# tactBell_revA.net
KiCad netlist of a schematic drawn in EAGLE
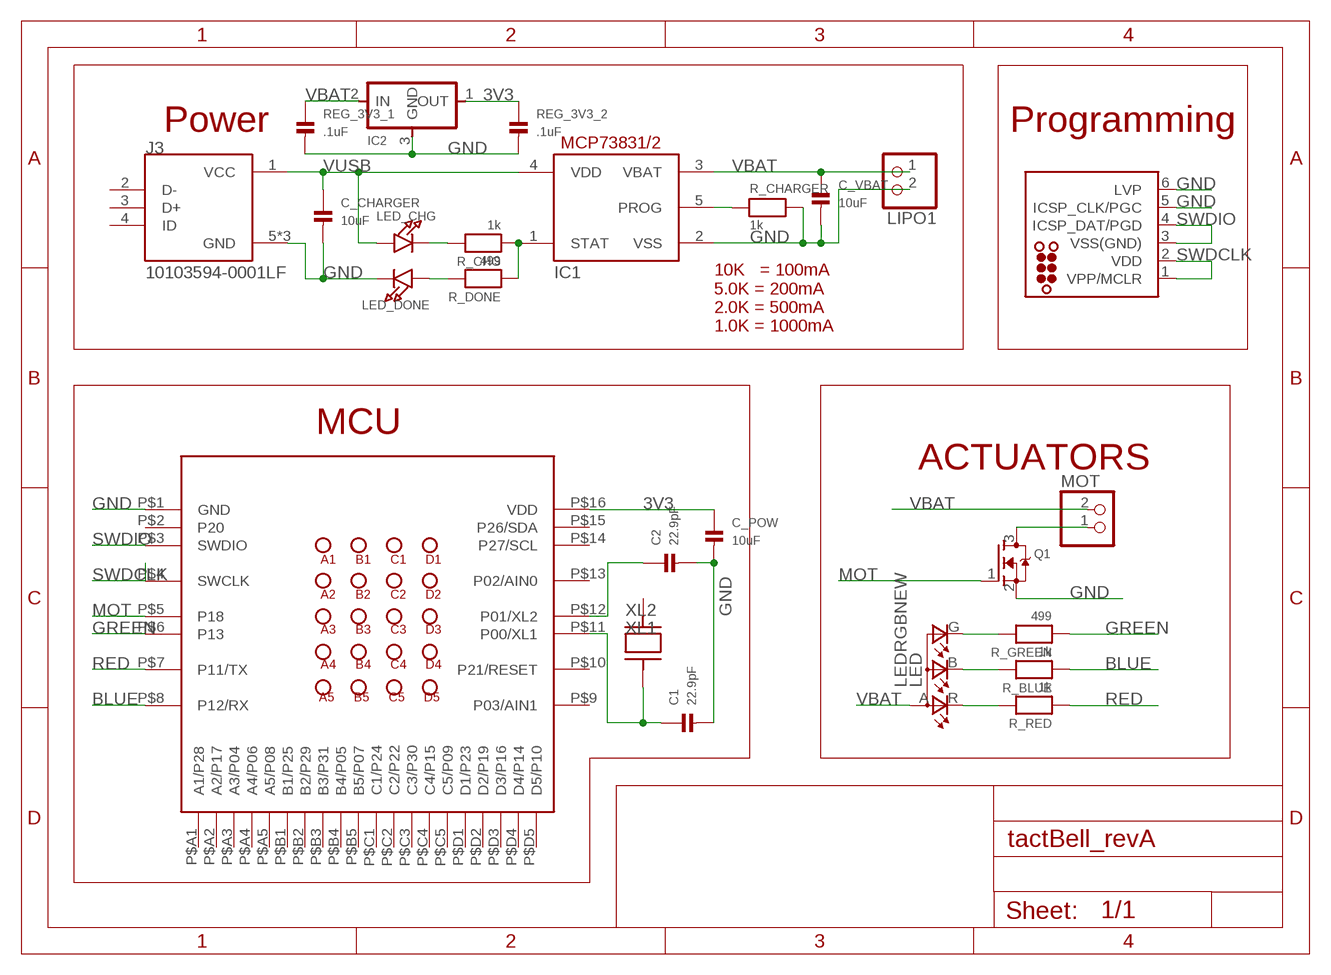
[diagram p0: schematic, sheet 1]

(export (version "E")
  (design (tool "Eeschema 10.0.6"))
  (components
    (comp (ref "C1")
      (value "22.9pF")
      (footprint "eagle-import:0603")
      (libsource (lib "eagle-import") (part "CAP_CERAMIC0603"))
    )
    (comp (ref "C2")
      (value "22.9pF")
      (footprint "eagle-import:0603")
      (libsource (lib "eagle-import") (part "CAP_CERAMIC0603"))
    )
    (comp (ref "C_CHARGER")
      (value "10uF")
      (footprint "eagle-import:0603")
      (libsource (lib "eagle-import") (part "CAP_CERAMIC0603"))
    )
    (comp (ref "C_POW")
      (value "10uF")
      (footprint "eagle-import:0603")
      (libsource (lib "eagle-import") (part "CAP_CERAMIC0603"))
    )
    (comp (ref "C_VBAT")
      (value "10uF")
      (footprint "eagle-import:0603")
      (libsource (lib "eagle-import") (part "CAP_CERAMIC0603"))
    )
    (comp (ref "IC1")
      (value "MCP73831/OT")
      (footprint "eagle-import:SOT23-5L")
      (libsource (lib "eagle-import") (part "MCP73831/OT"))
    )
    (comp (ref "IC2")
      (value "REGULATORSOT23")
      (footprint "eagle-import:SOT23")
      (libsource (lib "eagle-import") (part "REGULATORSOT23"))
    )
    (comp (ref "J1")
      (value "TC2030-MCP-NL")
      (footprint "eagle-import:TC2030-MCP-NL")
      (libsource (lib "eagle-import") (part "TC2030-MCP-NL"))
    )
    (comp (ref "J3")
      (value "10103594-0001LF")
      (footprint "eagle-import:FCI_10103594-0001LF")
      (fields (field (name "MF") "FCI"))
      (libsource (lib "eagle-import") (part "10103594-0001LF"))
    )
    (comp (ref "LED")
      (value "LEDRGBNEW")
      (footprint "eagle-import:P-LCC-4")
      (libsource (lib "eagle-import") (part "LEDRGBNEW"))
    )
    (comp (ref "LED_CHG")
      (value "LED0603")
      (footprint "eagle-import:CHIPLED_0603")
      (libsource (lib "eagle-import") (part "LED0603"))
    )
    (comp (ref "LED_DONE")
      (value "LED0603")
      (footprint "eagle-import:CHIPLED_0603")
      (libsource (lib "eagle-import") (part "LED0603"))
    )
    (comp (ref "LIPO1")
      (value "JST_2PIN-SMT-RA")
      (footprint "eagle-import:JST-PH-2-SMT-RA")
      (libsource (lib "eagle-import") (part "JST_2PIN-SMT-RA"))
    )
    (comp (ref "MOT")
      (value "JST_2PIN-SMT-RA")
      (footprint "eagle-import:JST-PH-2-SMT-RA")
      (libsource (lib "eagle-import") (part "JST_2PIN-SMT-RA"))
    )
    (comp (ref "Q1")
      (value "MOSFET-NREFLOW")
      (footprint "eagle-import:SOT23-R")
      (libsource (lib "eagle-import") (part "MOSFET-NREFLOW"))
    )
    (comp (ref "REG_3V3_1")
      (value ".1uF")
      (footprint "eagle-import:0603")
      (libsource (lib "eagle-import") (part "CAP_CERAMIC0603"))
    )
    (comp (ref "REG_3V3_2")
      (value ".1uF")
      (footprint "eagle-import:0603")
      (libsource (lib "eagle-import") (part "CAP_CERAMIC0603"))
    )
    (comp (ref "R_BLUE")
      (value "1k")
      (footprint "eagle-import:0603")
      (libsource (lib "eagle-import") (part "RESISTOR0603"))
    )
    (comp (ref "R_CHARGER")
      (value "1k")
      (footprint "eagle-import:0603")
      (libsource (lib "eagle-import") (part "RESISTOR0603"))
    )
    (comp (ref "R_CHG")
      (value "1k")
      (footprint "eagle-import:0603")
      (libsource (lib "eagle-import") (part "RESISTOR0603"))
    )
    (comp (ref "R_DONE")
      (value "499")
      (footprint "eagle-import:0603")
      (libsource (lib "eagle-import") (part "RESISTOR0603"))
    )
    (comp (ref "R_GREEN")
      (value "499")
      (footprint "eagle-import:0603")
      (libsource (lib "eagle-import") (part "RESISTOR0603"))
    )
    (comp (ref "R_RED")
      (value "1k")
      (footprint "eagle-import:0603")
      (libsource (lib "eagle-import") (part "RESISTOR0603"))
    )
    (comp (ref "U2")
      (value "BC832-V0")
      (footprint "eagle-import:BC832")
      (libsource (lib "eagle-import") (part "BC832-V0"))
    )
    (comp (ref "XL")
      (value "ECX-31B")
      (footprint "eagle-import:ECX-31B")
      (libsource (lib "eagle-import") (part "ECX-31B"))
    )
  )
  (nets
    (net (code "1") (name "/3V3") (class "Default")
      (node (ref "C_POW") (pin "1") (pinfunction "P$1_1") (pintype "passive"))
      (node (ref "IC2") (pin "1") (pinfunction "OUT_1") (pintype "bidirectional"))
      (node (ref "REG_3V3_2") (pin "1") (pinfunction "P$1_1") (pintype "passive"))
      (node (ref "U2") (pin "P$16") (pinfunction "VDD_P$16") (pintype "bidirectional"))
    )
    (net (code "2") (name "/BLUE") (class "Default")
      (node (ref "R_BLUE") (pin "1") (pinfunction "1_1") (pintype "passive"))
      (node (ref "U2") (pin "P$8") (pinfunction "P12/RX_P$8") (pintype "bidirectional"))
    )
    (net (code "3") (name "/GND") (class "Default")
      (node (ref "C1") (pin "2") (pinfunction "P$2_2") (pintype "passive"))
      (node (ref "C2") (pin "2") (pinfunction "P$2_2") (pintype "passive"))
      (node (ref "C_CHARGER") (pin "2") (pinfunction "P$2_2") (pintype "passive"))
      (node (ref "C_POW") (pin "2") (pinfunction "P$2_2") (pintype "passive"))
      (node (ref "C_VBAT") (pin "2") (pinfunction "P$2_2") (pintype "passive"))
      (node (ref "IC1") (pin "2") (pinfunction "VSS_2") (pintype "power_in"))
      (node (ref "IC2") (pin "3") (pinfunction "GND_3") (pintype "bidirectional"))
      (node (ref "J1") (pin "5") (pinfunction "ICSP_CLK/PGC_5") (pintype "output"))
      (node (ref "J1") (pin "6") (pinfunction "LVP_6") (pintype "bidirectional"))
      (node (ref "J3") (pin "5") (pinfunction "GND_5") (pintype "power_in"))
      (node (ref "J3") (pin "P3") (pinfunction "GND_P3") (pintype "power_in"))
      (node (ref "J3") (pin "P4") (pinfunction "GND_P4") (pintype "power_in"))
      (node (ref "LED_DONE") (pin "C") (pinfunction "C_C") (pintype "passive"))
      (node (ref "LIPO1") (pin "2") (pinfunction "1_2") (pintype "passive"))
      (node (ref "Q1") (pin "2") (pinfunction "S_2") (pintype "bidirectional"))
      (node (ref "REG_3V3_1") (pin "2") (pinfunction "P$2_2") (pintype "passive"))
      (node (ref "REG_3V3_2") (pin "2") (pinfunction "P$2_2") (pintype "passive"))
      (node (ref "R_CHARGER") (pin "2") (pinfunction "2_2") (pintype "passive"))
      (node (ref "U2") (pin "P$1") (pinfunction "GND_P$1") (pintype "bidirectional"))
    )
    (net (code "4") (name "/GREEN") (class "Default")
      (node (ref "R_GREEN") (pin "1") (pinfunction "1_1") (pintype "passive"))
      (node (ref "U2") (pin "P$6") (pinfunction "P13_P$6") (pintype "bidirectional"))
    )
    (net (code "5") (name "/MOT") (class "Default")
      (node (ref "Q1") (pin "1") (pinfunction "G_1") (pintype "bidirectional"))
      (node (ref "U2") (pin "P$5") (pinfunction "P18_P$5") (pintype "bidirectional"))
    )
    (net (code "6") (name "/RED") (class "Default")
      (node (ref "R_RED") (pin "1") (pinfunction "1_1") (pintype "passive"))
      (node (ref "U2") (pin "P$7") (pinfunction "P11/TX_P$7") (pintype "bidirectional"))
    )
    (net (code "7") (name "/SWDCLK") (class "Default")
      (node (ref "J1") (pin "1") (pinfunction "VPP/MCLR_1") (pintype "passive"))
      (node (ref "J1") (pin "2") (pinfunction "VDD_2") (pintype "power_in"))
      (node (ref "U2") (pin "P$4") (pinfunction "SWCLK_P$4") (pintype "bidirectional"))
    )
    (net (code "8") (name "/SWDIO") (class "Default")
      (node (ref "J1") (pin "3") (pinfunction "VSS(GND)_3") (pintype "power_in"))
      (node (ref "J1") (pin "4") (pinfunction "ICSP_DAT/PGD_4") (pintype "bidirectional"))
      (node (ref "U2") (pin "P$3") (pinfunction "SWDIO_P$3") (pintype "bidirectional"))
    )
    (net (code "9") (name "/VBAT") (class "Default")
      (node (ref "C_VBAT") (pin "1") (pinfunction "P$1_1") (pintype "passive"))
      (node (ref "IC1") (pin "3") (pinfunction "VBAT_3") (pintype "bidirectional"))
      (node (ref "IC2") (pin "2") (pinfunction "IN_2") (pintype "bidirectional"))
      (node (ref "LED") (pin "A") (pinfunction "A2_A") (pintype "passive"))
      (node (ref "LIPO1") (pin "1") (pinfunction "2_1") (pintype "passive"))
      (node (ref "MOT") (pin "2") (pinfunction "1_2") (pintype "passive"))
      (node (ref "REG_3V3_1") (pin "1") (pinfunction "P$1_1") (pintype "passive"))
    )
    (net (code "10") (name "/VUSB") (class "Default")
      (node (ref "C_CHARGER") (pin "1") (pinfunction "P$1_1") (pintype "passive"))
      (node (ref "IC1") (pin "4") (pinfunction "VDD_4") (pintype "power_in"))
      (node (ref "J3") (pin "1") (pinfunction "VCC_1") (pintype "power_in"))
      (node (ref "LED_CHG") (pin "A") (pinfunction "A_A") (pintype "passive"))
    )
    (net (code "11") (name "/XL1") (class "Default")
      (node (ref "C1") (pin "1") (pinfunction "P$1_1") (pintype "passive"))
      (node (ref "U2") (pin "P$11") (pinfunction "P00/XL1_P$11") (pintype "bidirectional"))
      (node (ref "XL") (pin "XL1") (pinfunction "XL1_XL1") (pintype "bidirectional"))
    )
    (net (code "12") (name "/XL2") (class "Default")
      (node (ref "C2") (pin "1") (pinfunction "P$1_1") (pintype "passive"))
      (node (ref "U2") (pin "P$12") (pinfunction "P01/XL2_P$12") (pintype "bidirectional"))
    )
    (net (code "13") (name "Net-(IC1-PROG)") (class "Default")
      (node (ref "IC1") (pin "5") (pinfunction "PROG_5") (pintype "input"))
      (node (ref "R_CHARGER") (pin "1") (pinfunction "1_1") (pintype "passive"))
    )
    (net (code "14") (name "Net-(IC1-STAT)") (class "Default")
      (node (ref "IC1") (pin "1") (pinfunction "STAT_1") (pintype "output"))
      (node (ref "R_CHG") (pin "1") (pinfunction "1_1") (pintype "passive"))
      (node (ref "R_DONE") (pin "1") (pinfunction "1_1") (pintype "passive"))
    )
    (net (code "15") (name "Net-(LED-CBLUE)") (class "Default")
      (node (ref "LED") (pin "B") (pinfunction "CBLUE_B") (pintype "passive"))
      (node (ref "R_BLUE") (pin "2") (pinfunction "2_2") (pintype "passive"))
    )
    (net (code "16") (name "Net-(LED-CGREEN)") (class "Default")
      (node (ref "LED") (pin "G") (pinfunction "CGREEN_G") (pintype "passive"))
      (node (ref "R_GREEN") (pin "2") (pinfunction "2_2") (pintype "passive"))
    )
    (net (code "17") (name "Net-(LED-CRED)") (class "Default")
      (node (ref "LED") (pin "R") (pinfunction "CRED_R") (pintype "passive"))
      (node (ref "R_RED") (pin "2") (pinfunction "2_2") (pintype "passive"))
    )
    (net (code "18") (name "Net-(LED_CHG-PadC)") (class "Default")
      (node (ref "LED_CHG") (pin "C") (pinfunction "C_C") (pintype "passive"))
      (node (ref "R_CHG") (pin "2") (pinfunction "2_2") (pintype "passive"))
    )
    (net (code "19") (name "Net-(LED_DONE-PadA)") (class "Default")
      (node (ref "LED_DONE") (pin "A") (pinfunction "A_A") (pintype "passive"))
      (node (ref "R_DONE") (pin "2") (pinfunction "2_2") (pintype "passive"))
    )
    (net (code "20") (name "Net-(MOT-2)") (class "Default")
      (node (ref "MOT") (pin "1") (pinfunction "2_1") (pintype "passive"))
      (node (ref "Q1") (pin "3") (pinfunction "D_3") (pintype "bidirectional"))
    )
    (net (code "21") (name "unconnected-(J3-D+-Pad3)") (class "Default")
      (node (ref "J3") (pin "3") (pinfunction "D+_3") (pintype "bidirectional"))
    )
    (net (code "22") (name "unconnected-(J3-D--Pad2)") (class "Default")
      (node (ref "J3") (pin "2") (pinfunction "D-_2") (pintype "bidirectional"))
    )
    (net (code "23") (name "unconnected-(J3-ID-Pad4)") (class "Default")
      (node (ref "J3") (pin "4") (pinfunction "ID_4") (pintype "bidirectional"))
    )
    (net (code "24") (name "unconnected-(U2-A1{slash}P28-PadP$A1)") (class "Default")
      (node (ref "U2") (pin "P$A1") (pinfunction "A1/P28_P$A1") (pintype "bidirectional"))
    )
    (net (code "25") (name "unconnected-(U2-A2{slash}P17-PadP$A2)") (class "Default")
      (node (ref "U2") (pin "P$A2") (pinfunction "A2/P17_P$A2") (pintype "bidirectional"))
    )
    (net (code "26") (name "unconnected-(U2-A3{slash}P04-PadP$A3)") (class "Default")
      (node (ref "U2") (pin "P$A3") (pinfunction "A3/P04_P$A3") (pintype "bidirectional"))
    )
    (net (code "27") (name "unconnected-(U2-A4{slash}P06-PadP$A4)") (class "Default")
      (node (ref "U2") (pin "P$A4") (pinfunction "A4/P06_P$A4") (pintype "bidirectional"))
    )
    (net (code "28") (name "unconnected-(U2-A5{slash}P08-PadP$A5)") (class "Default")
      (node (ref "U2") (pin "P$A5") (pinfunction "A5/P08_P$A5") (pintype "bidirectional"))
    )
    (net (code "29") (name "unconnected-(U2-B1{slash}P25-PadP$B1)") (class "Default")
      (node (ref "U2") (pin "P$B1") (pinfunction "B1/P25_P$B1") (pintype "bidirectional"))
    )
    (net (code "30") (name "unconnected-(U2-B2{slash}P29-PadP$B2)") (class "Default")
      (node (ref "U2") (pin "P$B2") (pinfunction "B2/P29_P$B2") (pintype "bidirectional"))
    )
    (net (code "31") (name "unconnected-(U2-B3{slash}P31-PadP$B3)") (class "Default")
      (node (ref "U2") (pin "P$B3") (pinfunction "B3/P31_P$B3") (pintype "bidirectional"))
    )
    (net (code "32") (name "unconnected-(U2-B4{slash}P05-PadP$B4)") (class "Default")
      (node (ref "U2") (pin "P$B4") (pinfunction "B4/P05_P$B4") (pintype "bidirectional"))
    )
    (net (code "33") (name "unconnected-(U2-B5{slash}P07-PadP$B5)") (class "Default")
      (node (ref "U2") (pin "P$B5") (pinfunction "B5/P07_P$B5") (pintype "bidirectional"))
    )
    (net (code "34") (name "unconnected-(U2-C1{slash}P24-PadP$C1)") (class "Default")
      (node (ref "U2") (pin "P$C1") (pinfunction "C1/P24_P$C1") (pintype "bidirectional"))
    )
    (net (code "35") (name "unconnected-(U2-C2{slash}P22-PadP$C2)") (class "Default")
      (node (ref "U2") (pin "P$C2") (pinfunction "C2/P22_P$C2") (pintype "bidirectional"))
    )
    (net (code "36") (name "unconnected-(U2-C3{slash}P30-PadP$C3)") (class "Default")
      (node (ref "U2") (pin "P$C3") (pinfunction "C3/P30_P$C3") (pintype "bidirectional"))
    )
    (net (code "37") (name "unconnected-(U2-C4{slash}P15-PadP$C4)") (class "Default")
      (node (ref "U2") (pin "P$C4") (pinfunction "C4/P15_P$C4") (pintype "bidirectional"))
    )
    (net (code "38") (name "unconnected-(U2-C5{slash}P09-PadP$C5)") (class "Default")
      (node (ref "U2") (pin "P$C5") (pinfunction "C5/P09_P$C5") (pintype "bidirectional"))
    )
    (net (code "39") (name "unconnected-(U2-D1{slash}P23-PadP$D1)") (class "Default")
      (node (ref "U2") (pin "P$D1") (pinfunction "D1/P23_P$D1") (pintype "bidirectional"))
    )
    (net (code "40") (name "unconnected-(U2-D2{slash}P19-PadP$D2)") (class "Default")
      (node (ref "U2") (pin "P$D2") (pinfunction "D2/P19_P$D2") (pintype "bidirectional"))
    )
    (net (code "41") (name "unconnected-(U2-D3{slash}P16-PadP$D3)") (class "Default")
      (node (ref "U2") (pin "P$D3") (pinfunction "D3/P16_P$D3") (pintype "bidirectional"))
    )
    (net (code "42") (name "unconnected-(U2-D4{slash}P14-PadP$D4)") (class "Default")
      (node (ref "U2") (pin "P$D4") (pinfunction "D4/P14_P$D4") (pintype "bidirectional"))
    )
    (net (code "43") (name "unconnected-(U2-D5{slash}P10-PadP$D5)") (class "Default")
      (node (ref "U2") (pin "P$D5") (pinfunction "D5/P10_P$D5") (pintype "bidirectional"))
    )
    (net (code "44") (name "unconnected-(U2-P02{slash}AIN0-PadP$13)") (class "Default")
      (node (ref "U2") (pin "P$13") (pinfunction "P02/AIN0_P$13") (pintype "bidirectional"))
    )
    (net (code "45") (name "unconnected-(U2-P03{slash}AIN1-PadP$9)") (class "Default")
      (node (ref "U2") (pin "P$9") (pinfunction "P03/AIN1_P$9") (pintype "bidirectional"))
    )
    (net (code "46") (name "unconnected-(U2-P20-PadP$2)") (class "Default")
      (node (ref "U2") (pin "P$2") (pinfunction "P20_P$2") (pintype "bidirectional"))
    )
    (net (code "47") (name "unconnected-(U2-P21{slash}RESET-PadP$10)") (class "Default")
      (node (ref "U2") (pin "P$10") (pinfunction "P21/RESET_P$10") (pintype "bidirectional"))
    )
    (net (code "48") (name "unconnected-(U2-P26{slash}SDA-PadP$15)") (class "Default")
      (node (ref "U2") (pin "P$15") (pinfunction "P26/SDA_P$15") (pintype "bidirectional"))
    )
    (net (code "49") (name "unconnected-(U2-P27{slash}SCL-PadP$14)") (class "Default")
      (node (ref "U2") (pin "P$14") (pinfunction "P27/SCL_P$14") (pintype "bidirectional"))
    )
    (net (code "50") (name "unconnected-(XL-PadXL2)") (class "Default")
      (node (ref "XL") (pin "XL2") (pinfunction "XL2_XL2") (pintype "bidirectional"))
    )
  )
)
